# uart2dali_mr3020_2.net
KiCad netlist of a schematic drawn in EAGLE
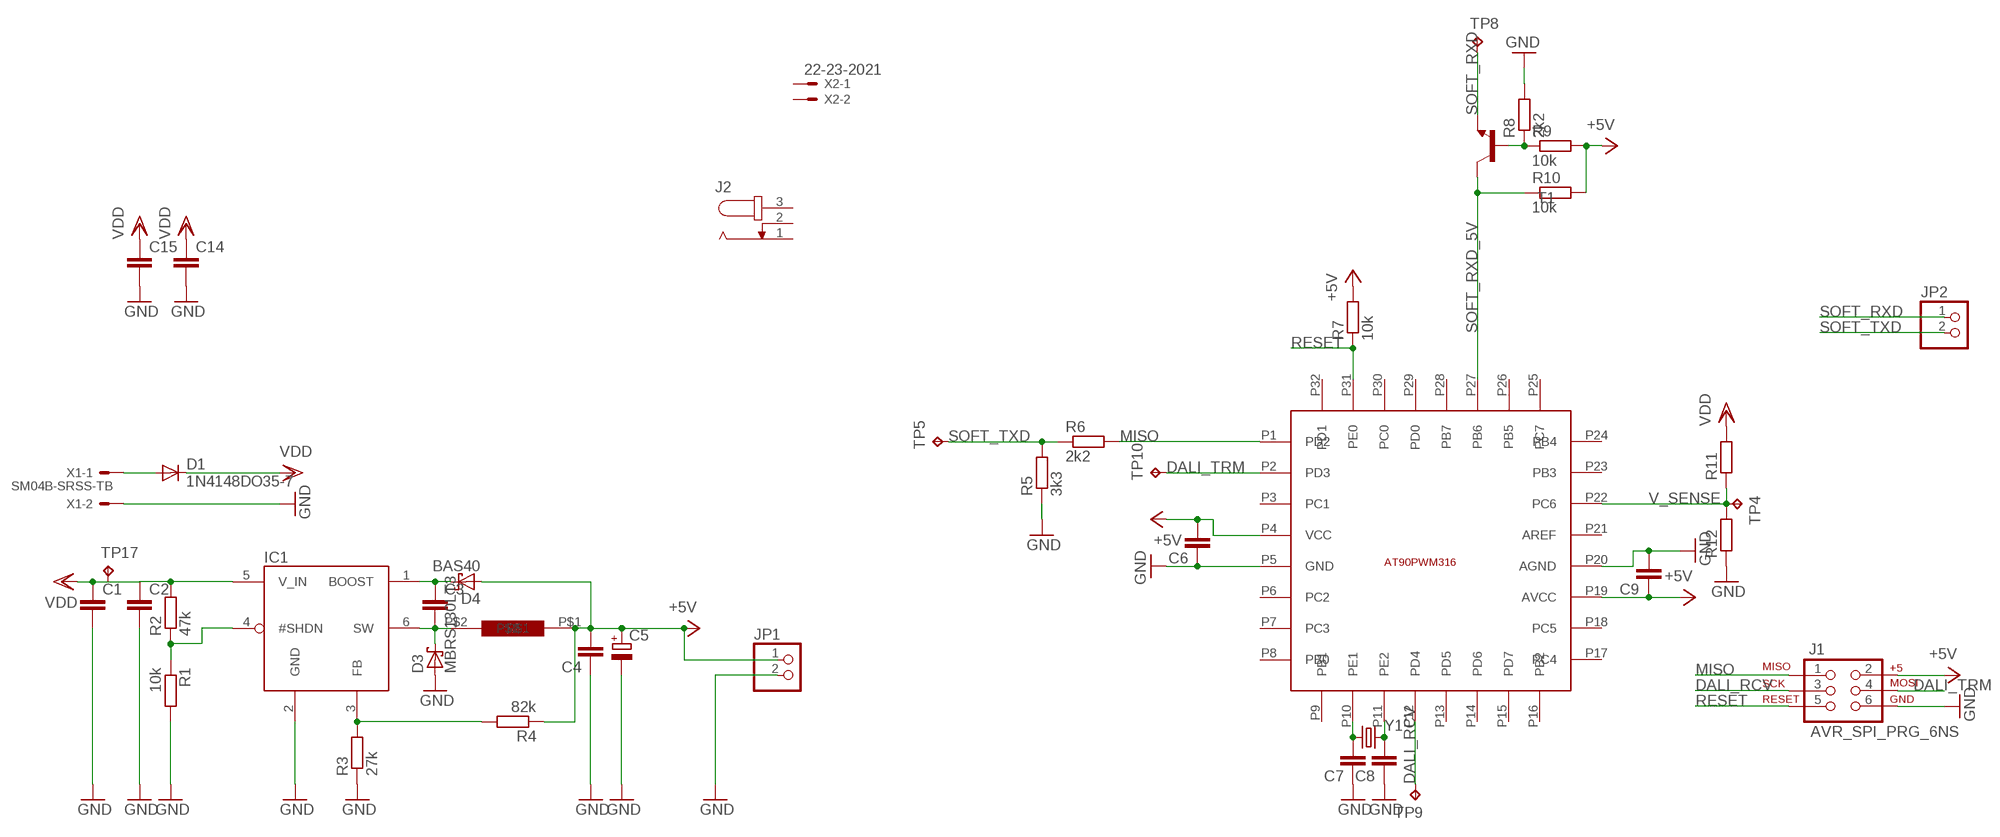
[diagram p0: schematic, sheet 1, part 1 of 2]
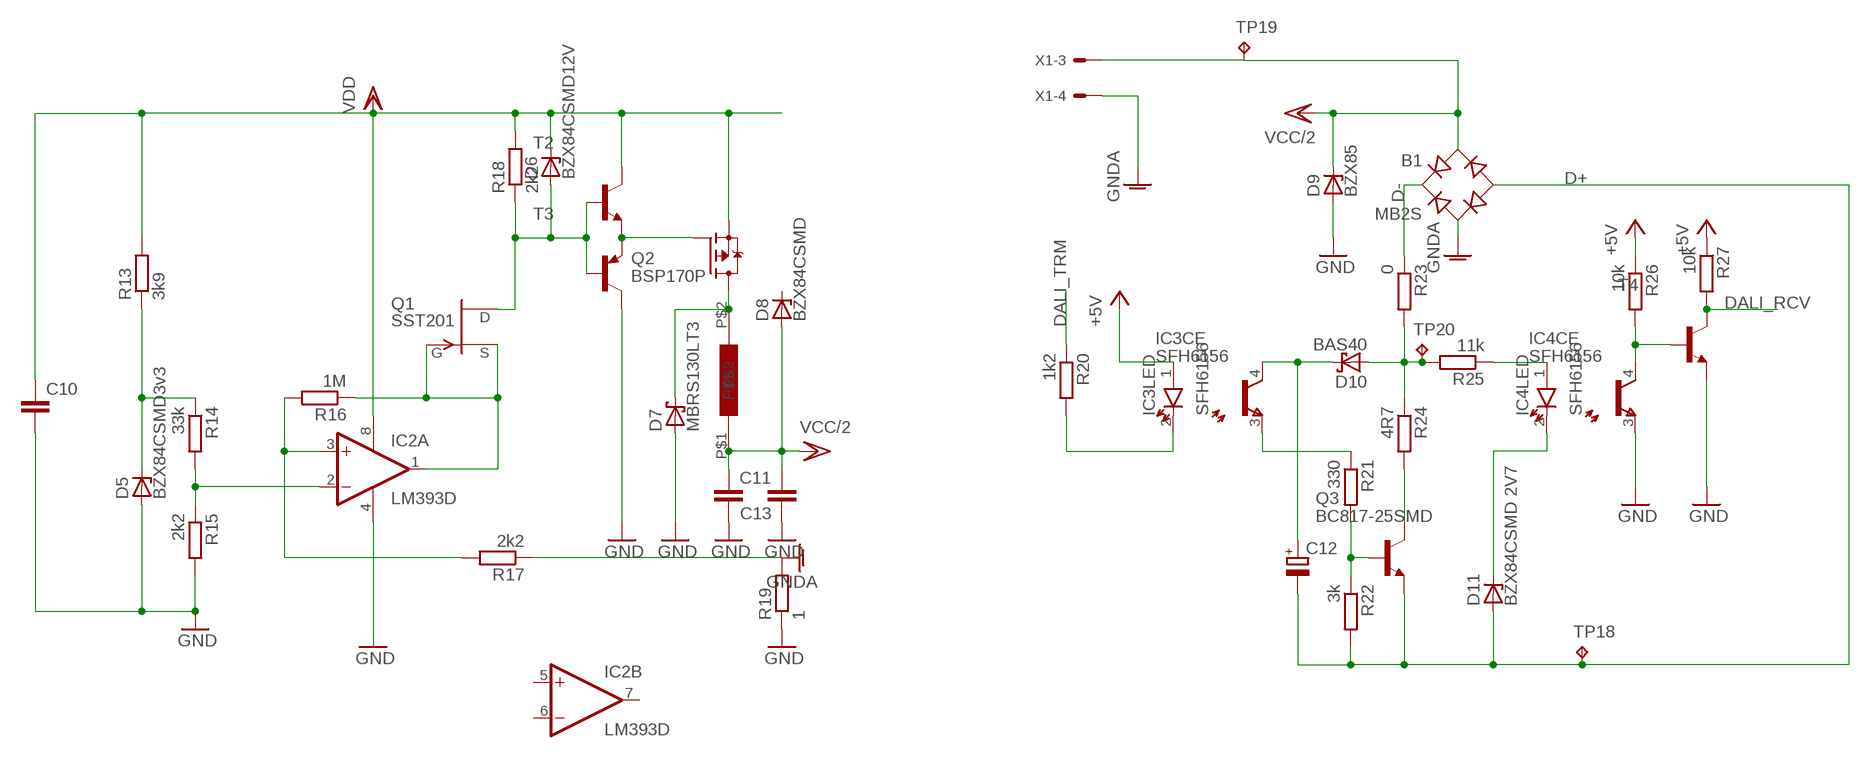
[diagram p1: schematic, sheet 1, part 2 of 2]

(export (version "E")
  (design (tool "Eeschema 10.0.6"))
  (components
    (comp (ref "B1")
      (value "MB2S")
      (footprint "eagle-import:SOIC-4")
      (libsource (lib "eagle-import") (part "MBS2"))
    )
    (comp (ref "C1")
      (value "C-EUC0805")
      (footprint "eagle-import:C0805")
      (libsource (lib "eagle-import") (part "C-EUC0805"))
    )
    (comp (ref "C2")
      (value "C-EUC0805")
      (footprint "eagle-import:C0805")
      (libsource (lib "eagle-import") (part "C-EUC0805"))
    )
    (comp (ref "C3")
      (value "C-EUC0805")
      (footprint "eagle-import:C0805")
      (libsource (lib "eagle-import") (part "C-EUC0805"))
    )
    (comp (ref "C4")
      (value "C-EUC0805")
      (footprint "eagle-import:C0805")
      (libsource (lib "eagle-import") (part "C-EUC0805"))
    )
    (comp (ref "C5")
      (value "CPOL-EUCT7343")
      (footprint "eagle-import:CT7343")
      (libsource (lib "eagle-import") (part "CPOL-EUCT7343"))
    )
    (comp (ref "C6")
      (value "C-EUC0603")
      (footprint "eagle-import:C0603")
      (libsource (lib "eagle-import") (part "C-EUC0603"))
    )
    (comp (ref "C7")
      (value "C-EUC0603")
      (footprint "eagle-import:C0603")
      (libsource (lib "eagle-import") (part "C-EUC0603"))
    )
    (comp (ref "C8")
      (value "C-EUC0603")
      (footprint "eagle-import:C0603")
      (libsource (lib "eagle-import") (part "C-EUC0603"))
    )
    (comp (ref "C9")
      (value "C-EUC0603")
      (footprint "eagle-import:C0603")
      (libsource (lib "eagle-import") (part "C-EUC0603"))
    )
    (comp (ref "C10")
      (value "C-EUC0603")
      (footprint "eagle-import:C0603")
      (libsource (lib "eagle-import") (part "C-EUC0603"))
    )
    (comp (ref "C11")
      (value "C-EUC0805")
      (footprint "eagle-import:C0805")
      (libsource (lib "eagle-import") (part "C-EUC0805"))
    )
    (comp (ref "C12")
      (value "CPOL-EUCT6032")
      (footprint "eagle-import:CT6032")
      (libsource (lib "eagle-import") (part "CPOL-EUCT6032"))
    )
    (comp (ref "C13")
      (value "C-EUC0805")
      (footprint "eagle-import:C0805")
      (libsource (lib "eagle-import") (part "C-EUC0805"))
    )
    (comp (ref "C14")
      (value "C-EUC0805")
      (footprint "eagle-import:C0805")
      (libsource (lib "eagle-import") (part "C-EUC0805"))
    )
    (comp (ref "C15")
      (value "C-EUC0805")
      (footprint "eagle-import:C0805")
      (libsource (lib "eagle-import") (part "C-EUC0805"))
    )
    (comp (ref "D1")
      (value "1N4148DO35-7")
      (footprint "eagle-import:DO35-7")
      (libsource (lib "eagle-import") (part "1N4148DO35-7"))
    )
    (comp (ref "D3")
      (value "MBRS130LT3")
      (footprint "eagle-import:SMB")
      (libsource (lib "eagle-import") (part "MBRS130LT3"))
    )
    (comp (ref "D4")
      (value "BAS40")
      (footprint "eagle-import:SOT23")
      (libsource (lib "eagle-import") (part "BAS40"))
    )
    (comp (ref "D5")
      (value "BZX84CSMD3v3")
      (footprint "eagle-import:TO236")
      (libsource (lib "eagle-import") (part "BZX84CSMD"))
    )
    (comp (ref "D6")
      (value "BZX84CSMD12V")
      (footprint "eagle-import:TO236")
      (libsource (lib "eagle-import") (part "BZX84CSMD"))
    )
    (comp (ref "D7")
      (value "MBRS130LT3")
      (footprint "eagle-import:SMB")
      (libsource (lib "eagle-import") (part "MBRS130LT3"))
    )
    (comp (ref "D8")
      (value "BZX84CSMD")
      (footprint "eagle-import:TO236")
      (libsource (lib "eagle-import") (part "BZX84CSMD"))
    )
    (comp (ref "D9")
      (value "BZX85")
      (footprint "eagle-import:DO41Z10")
      (libsource (lib "eagle-import") (part "BZX85"))
    )
    (comp (ref "D10")
      (value "BAS40")
      (footprint "eagle-import:SOT23")
      (libsource (lib "eagle-import") (part "BAS40"))
    )
    (comp (ref "D11")
      (value "BZX84CSMD 2V7")
      (footprint "eagle-import:TO236")
      (libsource (lib "eagle-import") (part "BZX84CSMD"))
    )
    (comp (ref "IC1")
      (value "LT1933ES6")
      (footprint "eagle-import:SOT23-6")
      (libsource (lib "eagle-import") (part "LT1933ES6"))
    )
    (comp (ref "IC2")
      (value "LM393D")
      (footprint "eagle-import:SO08")
      (libsource (lib "eagle-import") (part "LM393D"))
    )
    (comp (ref "IC3")
      (value "SFH6156")
      (footprint "eagle-import:SFH")
      (fields (field (name "MF") "VISHAY/TELEFUNKEN") (field (name "MPN") "SFH6156-4T"))
      (libsource (lib "eagle-import") (part "SFH6156"))
    )
    (comp (ref "IC4")
      (value "SFH6156")
      (footprint "eagle-import:SFH")
      (fields (field (name "MF") "VISHAY/TELEFUNKEN") (field (name "MPN") "SFH6156-4T"))
      (libsource (lib "eagle-import") (part "SFH6156"))
    )
    (comp (ref "J1")
      (value "AVR_SPI_PRG_6NS")
      (footprint "eagle-import:2X3-NS")
      (libsource (lib "eagle-import") (part "AVR_SPI_PRG_6NS"))
    )
    (comp (ref "J2")
      (value "JACK-PLUG1")
      (footprint "eagle-import:SPC4078")
      (libsource (lib "eagle-import") (part "JACK-PLUG1"))
    )
    (comp (ref "JP1")
      (value "PINHD-1X2")
      (footprint "eagle-import:1X02")
      (libsource (lib "eagle-import") (part "PINHD-1X2"))
    )
    (comp (ref "JP2")
      (value "PINHD-1X2")
      (footprint "eagle-import:1X02")
      (libsource (lib "eagle-import") (part "PINHD-1X2"))
    )
    (comp (ref "Q1")
      (value "SST201")
      (footprint "eagle-import:SOT23")
      (libsource (lib "eagle-import") (part "?20SST1"))
    )
    (comp (ref "Q2")
      (value "BSP170P")
      (footprint "eagle-import:SOT223")
      (libsource (lib "eagle-import") (part "BSP170P"))
    )
    (comp (ref "Q3")
      (value "BC817-25SMD")
      (footprint "eagle-import:SOT23-BEC")
      (libsource (lib "eagle-import") (part "BC817SMD-25"))
    )
    (comp (ref "R1")
      (value "10k")
      (footprint "eagle-import:R0603")
      (libsource (lib "eagle-import") (part "R-EU_R0603"))
    )
    (comp (ref "R2")
      (value "47k")
      (footprint "eagle-import:R0603")
      (libsource (lib "eagle-import") (part "R-EU_R0603"))
    )
    (comp (ref "R3")
      (value "27k")
      (footprint "eagle-import:R0603")
      (libsource (lib "eagle-import") (part "R-EU_R0603"))
    )
    (comp (ref "R4")
      (value "82k")
      (footprint "eagle-import:R0603")
      (libsource (lib "eagle-import") (part "R-EU_R0603"))
    )
    (comp (ref "R5")
      (value "3k3")
      (footprint "eagle-import:R0603")
      (libsource (lib "eagle-import") (part "R-EU_R0603"))
    )
    (comp (ref "R6")
      (value "2k2")
      (footprint "eagle-import:R0603")
      (libsource (lib "eagle-import") (part "R-EU_R0603"))
    )
    (comp (ref "R7")
      (value "10k")
      (footprint "eagle-import:R0603")
      (libsource (lib "eagle-import") (part "R-EU_R0603"))
    )
    (comp (ref "R8")
      (value "2k2")
      (footprint "eagle-import:R0603")
      (libsource (lib "eagle-import") (part "R-EU_R0603"))
    )
    (comp (ref "R9")
      (value "10k")
      (footprint "eagle-import:R0603")
      (libsource (lib "eagle-import") (part "R-EU_R0603"))
    )
    (comp (ref "R10")
      (value "10k")
      (footprint "eagle-import:R0603")
      (libsource (lib "eagle-import") (part "R-EU_R0603"))
    )
    (comp (ref "R11")
      (value "R-EU_R0603")
      (footprint "eagle-import:R0603")
      (libsource (lib "eagle-import") (part "R-EU_R0603"))
    )
    (comp (ref "R12")
      (value "R-EU_R0603")
      (footprint "eagle-import:R0603")
      (libsource (lib "eagle-import") (part "R-EU_R0603"))
    )
    (comp (ref "R13")
      (value "3k9")
      (footprint "eagle-import:R0603")
      (libsource (lib "eagle-import") (part "R-EU_R0603"))
    )
    (comp (ref "R14")
      (value "33k")
      (footprint "eagle-import:R0603")
      (libsource (lib "eagle-import") (part "R-EU_R0603"))
    )
    (comp (ref "R15")
      (value "2k2")
      (footprint "eagle-import:R0603")
      (libsource (lib "eagle-import") (part "R-EU_R0603"))
    )
    (comp (ref "R16")
      (value "1M")
      (footprint "eagle-import:R0603")
      (libsource (lib "eagle-import") (part "R-EU_R0603"))
    )
    (comp (ref "R17")
      (value "2k2")
      (footprint "eagle-import:R0603")
      (libsource (lib "eagle-import") (part "R-EU_R0603"))
    )
    (comp (ref "R18")
      (value "2k2")
      (footprint "eagle-import:R0603")
      (libsource (lib "eagle-import") (part "R-EU_R0603"))
    )
    (comp (ref "R19")
      (value "1")
      (footprint "eagle-import:R0603")
      (libsource (lib "eagle-import") (part "R-EU_R0603"))
    )
    (comp (ref "R20")
      (value "1k2")
      (footprint "eagle-import:R0603")
      (libsource (lib "eagle-import") (part "R-EU_R0603"))
    )
    (comp (ref "R21")
      (value "330")
      (footprint "eagle-import:R0603")
      (libsource (lib "eagle-import") (part "R-EU_R0603"))
    )
    (comp (ref "R22")
      (value "3k")
      (footprint "eagle-import:R0603")
      (libsource (lib "eagle-import") (part "R-EU_R0603"))
    )
    (comp (ref "R23")
      (value "0")
      (footprint "eagle-import:R0603")
      (libsource (lib "eagle-import") (part "R-EU_R0603"))
    )
    (comp (ref "R24")
      (value "4R7")
      (footprint "eagle-import:R0603")
      (libsource (lib "eagle-import") (part "R-EU_R0603"))
    )
    (comp (ref "R25")
      (value "11k")
      (footprint "eagle-import:R0603")
      (libsource (lib "eagle-import") (part "R-EU_R0603"))
    )
    (comp (ref "R26")
      (value "10k")
      (footprint "eagle-import:R0603")
      (libsource (lib "eagle-import") (part "R-EU_R0603"))
    )
    (comp (ref "R27")
      (value "10k")
      (footprint "eagle-import:R0603")
      (libsource (lib "eagle-import") (part "R-EU_R0603"))
    )
    (comp (ref "T1")
      (value "MMBT3904LT1-NPN-SOT23-BEC")
      (footprint "eagle-import:SOT23-BEC")
      (libsource (lib "eagle-import") (part "-NPN-SOT23-BECMMBT3904LT1"))
    )
    (comp (ref "T2")
      (value "MMBT3904LT1-NPN-SOT23-BEC")
      (footprint "eagle-import:SOT23-BEC")
      (libsource (lib "eagle-import") (part "-NPN-SOT23-BECMMBT3904LT1"))
    )
    (comp (ref "T3")
      (value "MMBT3640LT1-PNP-SOT23-BEC")
      (footprint "eagle-import:SOT23-BEC")
      (libsource (lib "eagle-import") (part "-PNP-SOT23-BECMMBT3640LT1"))
    )
    (comp (ref "T4")
      (value "MMBT3904LT1-NPN-SOT23-BEC")
      (footprint "eagle-import:SOT23-BEC")
      (libsource (lib "eagle-import") (part "-NPN-SOT23-BECMMBT3904LT1"))
    )
    (comp (ref "TP4")
      (value "TPB1,27")
      (footprint "eagle-import:B1,27")
      (libsource (lib "eagle-import") (part "TPB1,27"))
    )
    (comp (ref "TP5")
      (value "TPB1,27")
      (footprint "eagle-import:B1,27")
      (libsource (lib "eagle-import") (part "TPB1,27"))
    )
    (comp (ref "TP8")
      (value "TPB1,27")
      (footprint "eagle-import:B1,27")
      (libsource (lib "eagle-import") (part "TPB1,27"))
    )
    (comp (ref "TP9")
      (value "TPB1,27")
      (footprint "eagle-import:B1,27")
      (libsource (lib "eagle-import") (part "TPB1,27"))
    )
    (comp (ref "TP10")
      (value "TPB1,27")
      (footprint "eagle-import:B1,27")
      (libsource (lib "eagle-import") (part "TPB1,27"))
    )
    (comp (ref "TP17")
      (value "TPB1,27")
      (footprint "eagle-import:B1,27")
      (libsource (lib "eagle-import") (part "TPB1,27"))
    )
    (comp (ref "TP18")
      (value "TPB1,27")
      (footprint "eagle-import:B1,27")
      (libsource (lib "eagle-import") (part "TPB1,27"))
    )
    (comp (ref "TP19")
      (value "TPB1,27")
      (footprint "eagle-import:B1,27")
      (libsource (lib "eagle-import") (part "TPB1,27"))
    )
    (comp (ref "TP20")
      (value "TPB1,27")
      (footprint "eagle-import:B1,27")
      (libsource (lib "eagle-import") (part "TPB1,27"))
    )
    (comp (ref "U$1")
      (value "KMP_2330_UNSHIELDED")
      (footprint "eagle-import:KMP_2330_UNSHIELDED")
      (libsource (lib "eagle-import") (part "KMP_2330_UNSHIELDED"))
    )
    (comp (ref "U$2")
      (value "AT90PWM316")
      (footprint "eagle-import:QFN32_7MM")
      (libsource (lib "eagle-import") (part "AT90PWM316"))
    )
    (comp (ref "U$3")
      (value "SDR0805")
      (footprint "eagle-import:SDR0805")
      (libsource (lib "eagle-import") (part "SDR0805"))
    )
    (comp (ref "X1")
      (value "SM04B-SRSS-TB")
      (footprint "eagle-import:SM04B-SRSS-TB")
      (libsource (lib "eagle-import") (part "?M04B-SRSS-TBS"))
    )
    (comp (ref "X2")
      (value "22-23-2021")
      (footprint "eagle-import:22-23-2021")
      (fields (field (name "MF") "MOLEX"))
      (libsource (lib "eagle-import") (part "22-23-2021"))
    )
    (comp (ref "Y1")
      (value "CRYSTALTXC-7A")
      (footprint "eagle-import:CRYSTAL-TXC-7A")
      (libsource (lib "eagle-import") (part "CRYSTALTXC-7A"))
    )
  )
  (nets
    (net (code "1") (name "+5V") (class "Default")
      (node (ref "C4") (pin "2") (pinfunction "2_2") (pintype "passive"))
      (node (ref "C5") (pin "+") (pinfunction "+_+") (pintype "passive"))
      (node (ref "C6") (pin "2") (pinfunction "2_2") (pintype "passive"))
      (node (ref "C9") (pin "1") (pinfunction "1_1") (pintype "passive"))
      (node (ref "D4") (pin "1") (pinfunction "A_1") (pintype "passive"))
      (node (ref "IC3") (pin "1") (pinfunction "A_1") (pintype "bidirectional"))
      (node (ref "J1") (pin "2") (pinfunction "2_2") (pintype "passive"))
      (node (ref "JP1") (pin "1") (pinfunction "1_1") (pintype "passive"))
      (node (ref "R10") (pin "2") (pinfunction "2_2") (pintype "passive"))
      (node (ref "R26") (pin "1") (pinfunction "1_1") (pintype "passive"))
      (node (ref "R27") (pin "1") (pinfunction "1_1") (pintype "passive"))
      (node (ref "R4") (pin "1") (pinfunction "1_1") (pintype "passive"))
      (node (ref "R7") (pin "2") (pinfunction "2_2") (pintype "passive"))
      (node (ref "R9") (pin "2") (pinfunction "2_2") (pintype "passive"))
      (node (ref "U$1") (pin "P$1") (pinfunction "P$1_P$1") (pintype "bidirectional"))
      (node (ref "U$2") (pin "P19") (pinfunction "AVCC_P19") (pintype "bidirectional"))
      (node (ref "U$2") (pin "P4") (pinfunction "VCC_P4") (pintype "bidirectional"))
    )
    (net (code "2") (name "/D+") (class "Default")
      (node (ref "B1") (pin "-") (pinfunction "-_-") (pintype "passive"))
      (node (ref "C12") (pin "-") (pinfunction "-_-") (pintype "passive"))
      (node (ref "D11") (pin "A") (pinfunction "A_A") (pintype "passive"))
      (node (ref "Q3") (pin "E") (pinfunction "E_E") (pintype "passive"))
      (node (ref "R22") (pin "2") (pinfunction "2_2") (pintype "passive"))
      (node (ref "TP18") (pin "TP") (pinfunction "TP_TP") (pintype "input"))
    )
    (net (code "3") (name "/D-") (class "Default")
      (node (ref "B1") (pin "+") (pinfunction "+_+") (pintype "passive"))
      (node (ref "R23") (pin "1") (pinfunction "1_1") (pintype "passive"))
    )
    (net (code "4") (name "/DALI_RCV") (class "Default")
      (node (ref "IC4") (pin "4") (pinfunction "C_4") (pintype "bidirectional"))
      (node (ref "J1") (pin "3") (pinfunction "3_3") (pintype "passive"))
      (node (ref "R26") (pin "2") (pinfunction "2_2") (pintype "passive"))
      (node (ref "R27") (pin "2") (pinfunction "2_2") (pintype "passive"))
      (node (ref "T4") (pin "B") (pinfunction "B_B") (pintype "passive"))
      (node (ref "T4") (pin "C") (pinfunction "C_C") (pintype "passive"))
      (node (ref "TP9") (pin "TP") (pinfunction "TP_TP") (pintype "input"))
      (node (ref "U$2") (pin "P12") (pinfunction "PD4_P12") (pintype "bidirectional"))
    )
    (net (code "5") (name "/DALI_TRM") (class "Default")
      (node (ref "J1") (pin "4") (pinfunction "4_4") (pintype "passive"))
      (node (ref "R20") (pin "1") (pinfunction "1_1") (pintype "passive"))
      (node (ref "TP10") (pin "TP") (pinfunction "TP_TP") (pintype "input"))
      (node (ref "U$2") (pin "P2") (pinfunction "PD3_P2") (pintype "bidirectional"))
    )
    (net (code "6") (name "/MISO") (class "Default")
      (node (ref "J1") (pin "1") (pinfunction "1_1") (pintype "passive"))
      (node (ref "R6") (pin "2") (pinfunction "2_2") (pintype "passive"))
      (node (ref "U$2") (pin "P1") (pinfunction "PD2_P1") (pintype "bidirectional"))
    )
    (net (code "7") (name "/RESET") (class "Default")
      (node (ref "J1") (pin "5") (pinfunction "5_5") (pintype "passive"))
      (node (ref "R7") (pin "1") (pinfunction "1_1") (pintype "passive"))
      (node (ref "U$2") (pin "P31") (pinfunction "PE0_P31") (pintype "bidirectional"))
    )
    (net (code "8") (name "/SOFT_RXD") (class "Default")
      (node (ref "JP2") (pin "1") (pinfunction "1_1") (pintype "passive"))
      (node (ref "T1") (pin "E") (pinfunction "E_E") (pintype "passive"))
      (node (ref "TP8") (pin "TP") (pinfunction "TP_TP") (pintype "input"))
    )
    (net (code "9") (name "/SOFT_RXD_5V") (class "Default")
      (node (ref "R10") (pin "1") (pinfunction "1_1") (pintype "passive"))
      (node (ref "T1") (pin "C") (pinfunction "C_C") (pintype "passive"))
      (node (ref "U$2") (pin "P27") (pinfunction "PB6_P27") (pintype "bidirectional"))
    )
    (net (code "10") (name "/SOFT_TXD") (class "Default")
      (node (ref "JP2") (pin "2") (pinfunction "2_2") (pintype "passive"))
      (node (ref "R5") (pin "2") (pinfunction "2_2") (pintype "passive"))
      (node (ref "R6") (pin "1") (pinfunction "1_1") (pintype "passive"))
      (node (ref "TP5") (pin "TP") (pinfunction "TP_TP") (pintype "input"))
    )
    (net (code "11") (name "/V_SENSE") (class "Default")
      (node (ref "R11") (pin "1") (pinfunction "1_1") (pintype "passive"))
      (node (ref "R12") (pin "2") (pinfunction "2_2") (pintype "passive"))
      (node (ref "TP4") (pin "TP") (pinfunction "TP_TP") (pintype "input"))
      (node (ref "U$2") (pin "P22") (pinfunction "PC6_P22") (pintype "bidirectional"))
    )
    (net (code "12") (name "GND") (class "Default")
      (node (ref "C1") (pin "2") (pinfunction "2_2") (pintype "passive"))
      (node (ref "C10") (pin "2") (pinfunction "2_2") (pintype "passive"))
      (node (ref "C11") (pin "2") (pinfunction "2_2") (pintype "passive"))
      (node (ref "C13") (pin "1") (pinfunction "1_1") (pintype "passive"))
      (node (ref "C14") (pin "2") (pinfunction "2_2") (pintype "passive"))
      (node (ref "C15") (pin "2") (pinfunction "2_2") (pintype "passive"))
      (node (ref "C2") (pin "2") (pinfunction "2_2") (pintype "passive"))
      (node (ref "C4") (pin "1") (pinfunction "1_1") (pintype "passive"))
      (node (ref "C5") (pin "-") (pinfunction "-_-") (pintype "passive"))
      (node (ref "C6") (pin "1") (pinfunction "1_1") (pintype "passive"))
      (node (ref "C7") (pin "1") (pinfunction "1_1") (pintype "passive"))
      (node (ref "C8") (pin "1") (pinfunction "1_1") (pintype "passive"))
      (node (ref "C9") (pin "2") (pinfunction "2_2") (pintype "passive"))
      (node (ref "D3") (pin "A") (pinfunction "A_A") (pintype "passive"))
      (node (ref "D5") (pin "A") (pinfunction "A_A") (pintype "passive"))
      (node (ref "D7") (pin "A") (pinfunction "A_A") (pintype "passive"))
      (node (ref "D9") (pin "A") (pinfunction "A_A") (pintype "passive"))
      (node (ref "IC1") (pin "2") (pinfunction "GND_2") (pintype "power_in"))
      (node (ref "IC2") (pin "4") (pinfunction "V-_4") (pintype "power_in"))
      (node (ref "IC4") (pin "3") (pinfunction "E_3") (pintype "bidirectional"))
      (node (ref "J1") (pin "6") (pinfunction "6_6") (pintype "passive"))
      (node (ref "JP1") (pin "2") (pinfunction "2_2") (pintype "passive"))
      (node (ref "R1") (pin "2") (pinfunction "2_2") (pintype "passive"))
      (node (ref "R12") (pin "1") (pinfunction "1_1") (pintype "passive"))
      (node (ref "R15") (pin "2") (pinfunction "2_2") (pintype "passive"))
      (node (ref "R19") (pin "1") (pinfunction "1_1") (pintype "passive"))
      (node (ref "R3") (pin "1") (pinfunction "1_1") (pintype "passive"))
      (node (ref "R5") (pin "1") (pinfunction "1_1") (pintype "passive"))
      (node (ref "R8") (pin "2") (pinfunction "2_2") (pintype "passive"))
      (node (ref "T3") (pin "C") (pinfunction "C_C") (pintype "passive"))
      (node (ref "T4") (pin "E") (pinfunction "E_E") (pintype "passive"))
      (node (ref "U$2") (pin "P20") (pinfunction "AGND_P20") (pintype "bidirectional"))
      (node (ref "U$2") (pin "P5") (pinfunction "GND_P5") (pintype "bidirectional"))
      (node (ref "X1") (pin "2") (pinfunction "S_2") (pintype "passive"))
    )
    (net (code "13") (name "GNDA") (class "Default")
      (node (ref "B1") (pin "~2") (pinfunction "AC2_~2") (pintype "passive"))
      (node (ref "R17") (pin "1") (pinfunction "1_1") (pintype "passive"))
      (node (ref "R19") (pin "2") (pinfunction "2_2") (pintype "passive"))
      (node (ref "X1") (pin "4") (pinfunction "S_4") (pintype "passive"))
    )
    (net (code "14") (name "Net-(D4-C)") (class "Default")
      (node (ref "C3") (pin "1") (pinfunction "1_1") (pintype "passive"))
      (node (ref "D4") (pin "3") (pinfunction "C_3") (pintype "passive"))
      (node (ref "IC1") (pin "1") (pinfunction "BOOST_1") (pintype "passive"))
    )
    (net (code "15") (name "Net-(D5-PadC)") (class "Default")
      (node (ref "D5") (pin "C") (pinfunction "C_C") (pintype "passive"))
      (node (ref "R13") (pin "1") (pinfunction "1_1") (pintype "passive"))
      (node (ref "R14") (pin "1") (pinfunction "1_1") (pintype "passive"))
    )
    (net (code "16") (name "Net-(D7-PadC)") (class "Default")
      (node (ref "D7") (pin "C") (pinfunction "C_C") (pintype "passive"))
      (node (ref "Q2") (pin "2") (pinfunction "D_2") (pintype "passive"))
      (node (ref "Q2") (pin "4") (pinfunction "D_4") (pintype "passive"))
      (node (ref "U$3") (pin "P$2") (pinfunction "P$2_P$2") (pintype "bidirectional"))
    )
    (net (code "17") (name "Net-(D10-A)") (class "Default")
      (node (ref "D10") (pin "1") (pinfunction "A_1") (pintype "passive"))
      (node (ref "R23") (pin "2") (pinfunction "2_2") (pintype "passive"))
      (node (ref "R24") (pin "1") (pinfunction "1_1") (pintype "passive"))
      (node (ref "R25") (pin "2") (pinfunction "2_2") (pintype "passive"))
      (node (ref "TP20") (pin "TP") (pinfunction "TP_TP") (pintype "input"))
    )
    (net (code "18") (name "Net-(D10-C)") (class "Default")
      (node (ref "C12") (pin "+") (pinfunction "+_+") (pintype "passive"))
      (node (ref "D10") (pin "3") (pinfunction "C_3") (pintype "passive"))
      (node (ref "IC3") (pin "4") (pinfunction "C_4") (pintype "bidirectional"))
    )
    (net (code "19") (name "Net-(IC1-#SHDN)") (class "Default")
      (node (ref "IC1") (pin "4") (pinfunction "#SHDN_4") (pintype "passive"))
      (node (ref "R1") (pin "1") (pinfunction "1_1") (pintype "passive"))
      (node (ref "R2") (pin "1") (pinfunction "1_1") (pintype "passive"))
    )
    (net (code "20") (name "Net-(IC1-FB)") (class "Default")
      (node (ref "IC1") (pin "3") (pinfunction "FB_3") (pintype "passive"))
      (node (ref "R3") (pin "2") (pinfunction "2_2") (pintype "passive"))
      (node (ref "R4") (pin "2") (pinfunction "2_2") (pintype "passive"))
    )
    (net (code "21") (name "Net-(IC1-SW)") (class "Default")
      (node (ref "C3") (pin "2") (pinfunction "2_2") (pintype "passive"))
      (node (ref "D3") (pin "C") (pinfunction "C_C") (pintype "passive"))
      (node (ref "IC1") (pin "6") (pinfunction "SW_6") (pintype "passive"))
      (node (ref "U$1") (pin "P$2") (pinfunction "P$2_P$2") (pintype "bidirectional"))
    )
    (net (code "22") (name "Net-(IC2A-+IN)") (class "Default")
      (node (ref "IC2") (pin "3") (pinfunction "+IN_3") (pintype "input"))
      (node (ref "R16") (pin "2") (pinfunction "2_2") (pintype "passive"))
      (node (ref "R17") (pin "2") (pinfunction "2_2") (pintype "passive"))
    )
    (net (code "23") (name "Net-(IC2A--IN)") (class "Default")
      (node (ref "IC2") (pin "2") (pinfunction "-IN_2") (pintype "input"))
      (node (ref "R14") (pin "2") (pinfunction "2_2") (pintype "passive"))
      (node (ref "R15") (pin "1") (pinfunction "1_1") (pintype "passive"))
    )
    (net (code "24") (name "Net-(IC2A-OUT)") (class "Default")
      (node (ref "IC2") (pin "1") (pinfunction "OUT_1") (pintype "output"))
      (node (ref "Q1") (pin "2") (pinfunction "S_2") (pintype "passive"))
      (node (ref "Q1") (pin "3") (pinfunction "G_3") (pintype "passive"))
      (node (ref "R16") (pin "1") (pinfunction "1_1") (pintype "passive"))
    )
    (net (code "25") (name "Net-(IC3A-E)") (class "Default")
      (node (ref "IC3") (pin "3") (pinfunction "E_3") (pintype "bidirectional"))
      (node (ref "R21") (pin "1") (pinfunction "1_1") (pintype "passive"))
    )
    (net (code "26") (name "Net-(IC3B-K)") (class "Default")
      (node (ref "IC3") (pin "2") (pinfunction "K_2") (pintype "bidirectional"))
      (node (ref "R20") (pin "2") (pinfunction "2_2") (pintype "passive"))
    )
    (net (code "27") (name "Net-(IC4B-A)") (class "Default")
      (node (ref "IC4") (pin "1") (pinfunction "A_1") (pintype "bidirectional"))
      (node (ref "R25") (pin "1") (pinfunction "1_1") (pintype "passive"))
    )
    (net (code "28") (name "Net-(IC4B-K)") (class "Default")
      (node (ref "D11") (pin "C") (pinfunction "C_C") (pintype "passive"))
      (node (ref "IC4") (pin "2") (pinfunction "K_2") (pintype "bidirectional"))
    )
    (net (code "29") (name "Net-(Q1-D)") (class "Default")
      (node (ref "D6") (pin "A") (pinfunction "A_A") (pintype "passive"))
      (node (ref "Q1") (pin "1") (pinfunction "D_1") (pintype "passive"))
      (node (ref "R18") (pin "1") (pinfunction "1_1") (pintype "passive"))
      (node (ref "T2") (pin "B") (pinfunction "B_B") (pintype "passive"))
      (node (ref "T3") (pin "B") (pinfunction "B_B") (pintype "passive"))
    )
    (net (code "30") (name "Net-(Q2-G)") (class "Default")
      (node (ref "Q2") (pin "1") (pinfunction "G_1") (pintype "passive"))
      (node (ref "T2") (pin "E") (pinfunction "E_E") (pintype "passive"))
      (node (ref "T3") (pin "E") (pinfunction "E_E") (pintype "passive"))
    )
    (net (code "31") (name "Net-(Q3-PadB)") (class "Default")
      (node (ref "Q3") (pin "B") (pinfunction "B_B") (pintype "passive"))
      (node (ref "R21") (pin "2") (pinfunction "2_2") (pintype "passive"))
      (node (ref "R22") (pin "1") (pinfunction "1_1") (pintype "passive"))
    )
    (net (code "32") (name "Net-(Q3-PadC)") (class "Default")
      (node (ref "Q3") (pin "C") (pinfunction "C_C") (pintype "passive"))
      (node (ref "R24") (pin "2") (pinfunction "2_2") (pintype "passive"))
    )
    (net (code "33") (name "Net-(R8-Pad1)") (class "Default")
      (node (ref "R8") (pin "1") (pinfunction "1_1") (pintype "passive"))
      (node (ref "R9") (pin "1") (pinfunction "1_1") (pintype "passive"))
      (node (ref "T1") (pin "B") (pinfunction "B_B") (pintype "passive"))
    )
    (net (code "34") (name "Net-(U$2-PE1)") (class "Default")
      (node (ref "C7") (pin "2") (pinfunction "2_2") (pintype "passive"))
      (node (ref "U$2") (pin "P10") (pinfunction "PE1_P10") (pintype "bidirectional"))
      (node (ref "Y1") (pin "P$1") (pinfunction "1_P$1") (pintype "passive"))
    )
    (net (code "35") (name "Net-(U$2-PE2)") (class "Default")
      (node (ref "C8") (pin "2") (pinfunction "2_2") (pintype "passive"))
      (node (ref "U$2") (pin "P11") (pinfunction "PE2_P11") (pintype "bidirectional"))
      (node (ref "Y1") (pin "P$2") (pinfunction "2_P$2") (pintype "passive"))
    )
    (net (code "36") (name "Net-(X1A-S)") (class "Default")
      (node (ref "D1") (pin "A") (pinfunction "A_A") (pintype "passive"))
      (node (ref "X1") (pin "1") (pinfunction "S_1") (pintype "passive"))
    )
    (net (code "37") (name "VCC{slash}2") (class "Default")
      (node (ref "B1") (pin "~1") (pinfunction "AC1_~1") (pintype "passive"))
      (node (ref "C11") (pin "1") (pinfunction "1_1") (pintype "passive"))
      (node (ref "C13") (pin "2") (pinfunction "2_2") (pintype "passive"))
      (node (ref "D8") (pin "A") (pinfunction "A_A") (pintype "passive"))
      (node (ref "D9") (pin "C") (pinfunction "C_C") (pintype "passive"))
      (node (ref "TP19") (pin "TP") (pinfunction "TP_TP") (pintype "input"))
      (node (ref "U$3") (pin "P$1") (pinfunction "P$1_P$1") (pintype "bidirectional"))
      (node (ref "X1") (pin "3") (pinfunction "S_3") (pintype "passive"))
    )
    (net (code "38") (name "VDD") (class "Default")
      (node (ref "C1") (pin "1") (pinfunction "1_1") (pintype "passive"))
      (node (ref "C10") (pin "1") (pinfunction "1_1") (pintype "passive"))
      (node (ref "C14") (pin "1") (pinfunction "1_1") (pintype "passive"))
      (node (ref "C15") (pin "1") (pinfunction "1_1") (pintype "passive"))
      (node (ref "C2") (pin "1") (pinfunction "1_1") (pintype "passive"))
      (node (ref "D1") (pin "C") (pinfunction "C_C") (pintype "passive"))
      (node (ref "D6") (pin "C") (pinfunction "C_C") (pintype "passive"))
      (node (ref "IC1") (pin "5") (pinfunction "V_IN_5") (pintype "passive"))
      (node (ref "IC2") (pin "8") (pinfunction "V+_8") (pintype "power_in"))
      (node (ref "Q2") (pin "3") (pinfunction "S_3") (pintype "passive"))
      (node (ref "R11") (pin "2") (pinfunction "2_2") (pintype "passive"))
      (node (ref "R13") (pin "2") (pinfunction "2_2") (pintype "passive"))
      (node (ref "R18") (pin "2") (pinfunction "2_2") (pintype "passive"))
      (node (ref "R2") (pin "2") (pinfunction "2_2") (pintype "passive"))
      (node (ref "T2") (pin "C") (pinfunction "C_C") (pintype "passive"))
      (node (ref "TP17") (pin "TP") (pinfunction "TP_TP") (pintype "input"))
    )
    (net (code "39") (name "unconnected-(D8-PadC)") (class "Default")
      (node (ref "D8") (pin "C") (pinfunction "C_C") (pintype "passive"))
    )
    (net (code "40") (name "unconnected-(IC2B-+IN-Pad5)") (class "Default")
      (node (ref "IC2") (pin "5") (pinfunction "+IN_5") (pintype "input"))
    )
    (net (code "41") (name "unconnected-(IC2B--IN-Pad6)") (class "Default")
      (node (ref "IC2") (pin "6") (pinfunction "-IN_6") (pintype "input"))
    )
    (net (code "42") (name "unconnected-(IC2B-OUT-Pad7)") (class "Default")
      (node (ref "IC2") (pin "7") (pinfunction "OUT_7") (pintype "output"))
    )
    (net (code "43") (name "unconnected-(J2-Pad1)") (class "Default")
      (node (ref "J2") (pin "1") (pinfunction "1_1") (pintype "passive"))
    )
    (net (code "44") (name "unconnected-(J2-Pad2)") (class "Default")
      (node (ref "J2") (pin "2") (pinfunction "2_2") (pintype "passive"))
    )
    (net (code "45") (name "unconnected-(J2-Pad3)") (class "Default")
      (node (ref "J2") (pin "3") (pinfunction "3_3") (pintype "passive"))
    )
    (net (code "46") (name "unconnected-(U$2-AREF-PadP21)") (class "Default")
      (node (ref "U$2") (pin "P21") (pinfunction "AREF_P21") (pintype "bidirectional"))
    )
    (net (code "47") (name "unconnected-(U$2-PB0-PadP8)") (class "Default")
      (node (ref "U$2") (pin "P8") (pinfunction "PB0_P8") (pintype "bidirectional"))
    )
    (net (code "48") (name "unconnected-(U$2-PB1-PadP9)") (class "Default")
      (node (ref "U$2") (pin "P9") (pinfunction "PB1_P9") (pintype "bidirectional"))
    )
    (net (code "49") (name "unconnected-(U$2-PB2-PadP16)") (class "Default")
      (node (ref "U$2") (pin "P16") (pinfunction "PB2_P16") (pintype "bidirectional"))
    )
    (net (code "50") (name "unconnected-(U$2-PB3-PadP23)") (class "Default")
      (node (ref "U$2") (pin "P23") (pinfunction "PB3_P23") (pintype "bidirectional"))
    )
    (net (code "51") (name "unconnected-(U$2-PB4-PadP24)") (class "Default")
      (node (ref "U$2") (pin "P24") (pinfunction "PB4_P24") (pintype "bidirectional"))
    )
    (net (code "52") (name "unconnected-(U$2-PB5-PadP26)") (class "Default")
      (node (ref "U$2") (pin "P26") (pinfunction "PB5_P26") (pintype "bidirectional"))
    )
    (net (code "53") (name "unconnected-(U$2-PB7-PadP28)") (class "Default")
      (node (ref "U$2") (pin "P28") (pinfunction "PB7_P28") (pintype "bidirectional"))
    )
    (net (code "54") (name "unconnected-(U$2-PC0-PadP30)") (class "Default")
      (node (ref "U$2") (pin "P30") (pinfunction "PC0_P30") (pintype "bidirectional"))
    )
    (net (code "55") (name "unconnected-(U$2-PC1-PadP3)") (class "Default")
      (node (ref "U$2") (pin "P3") (pinfunction "PC1_P3") (pintype "bidirectional"))
    )
    (net (code "56") (name "unconnected-(U$2-PC2-PadP6)") (class "Default")
      (node (ref "U$2") (pin "P6") (pinfunction "PC2_P6") (pintype "bidirectional"))
    )
    (net (code "57") (name "unconnected-(U$2-PC3-PadP7)") (class "Default")
      (node (ref "U$2") (pin "P7") (pinfunction "PC3_P7") (pintype "bidirectional"))
    )
    (net (code "58") (name "unconnected-(U$2-PC4-PadP17)") (class "Default")
      (node (ref "U$2") (pin "P17") (pinfunction "PC4_P17") (pintype "bidirectional"))
    )
    (net (code "59") (name "unconnected-(U$2-PC5-PadP18)") (class "Default")
      (node (ref "U$2") (pin "P18") (pinfunction "PC5_P18") (pintype "bidirectional"))
    )
    (net (code "60") (name "unconnected-(U$2-PC7-PadP25)") (class "Default")
      (node (ref "U$2") (pin "P25") (pinfunction "PC7_P25") (pintype "bidirectional"))
    )
    (net (code "61") (name "unconnected-(U$2-PD0-PadP29)") (class "Default")
      (node (ref "U$2") (pin "P29") (pinfunction "PD0_P29") (pintype "bidirectional"))
    )
    (net (code "62") (name "unconnected-(U$2-PD1-PadP32)") (class "Default")
      (node (ref "U$2") (pin "P32") (pinfunction "PD1_P32") (pintype "bidirectional"))
    )
    (net (code "63") (name "unconnected-(U$2-PD5-PadP13)") (class "Default")
      (node (ref "U$2") (pin "P13") (pinfunction "PD5_P13") (pintype "bidirectional"))
    )
    (net (code "64") (name "unconnected-(U$2-PD6-PadP14)") (class "Default")
      (node (ref "U$2") (pin "P14") (pinfunction "PD6_P14") (pintype "bidirectional"))
    )
    (net (code "65") (name "unconnected-(U$2-PD7-PadP15)") (class "Default")
      (node (ref "U$2") (pin "P15") (pinfunction "PD7_P15") (pintype "bidirectional"))
    )
    (net (code "66") (name "unconnected-(X2A-S-Pad1)") (class "Default")
      (node (ref "X2") (pin "1") (pinfunction "S_1") (pintype "passive"))
    )
    (net (code "67") (name "unconnected-(X2B-S-Pad2)") (class "Default")
      (node (ref "X2") (pin "2") (pinfunction "S_2") (pintype "passive"))
    )
  )
)
